# TopSheet.net
KiCad netlist of a schematic drawn in Altium Designer
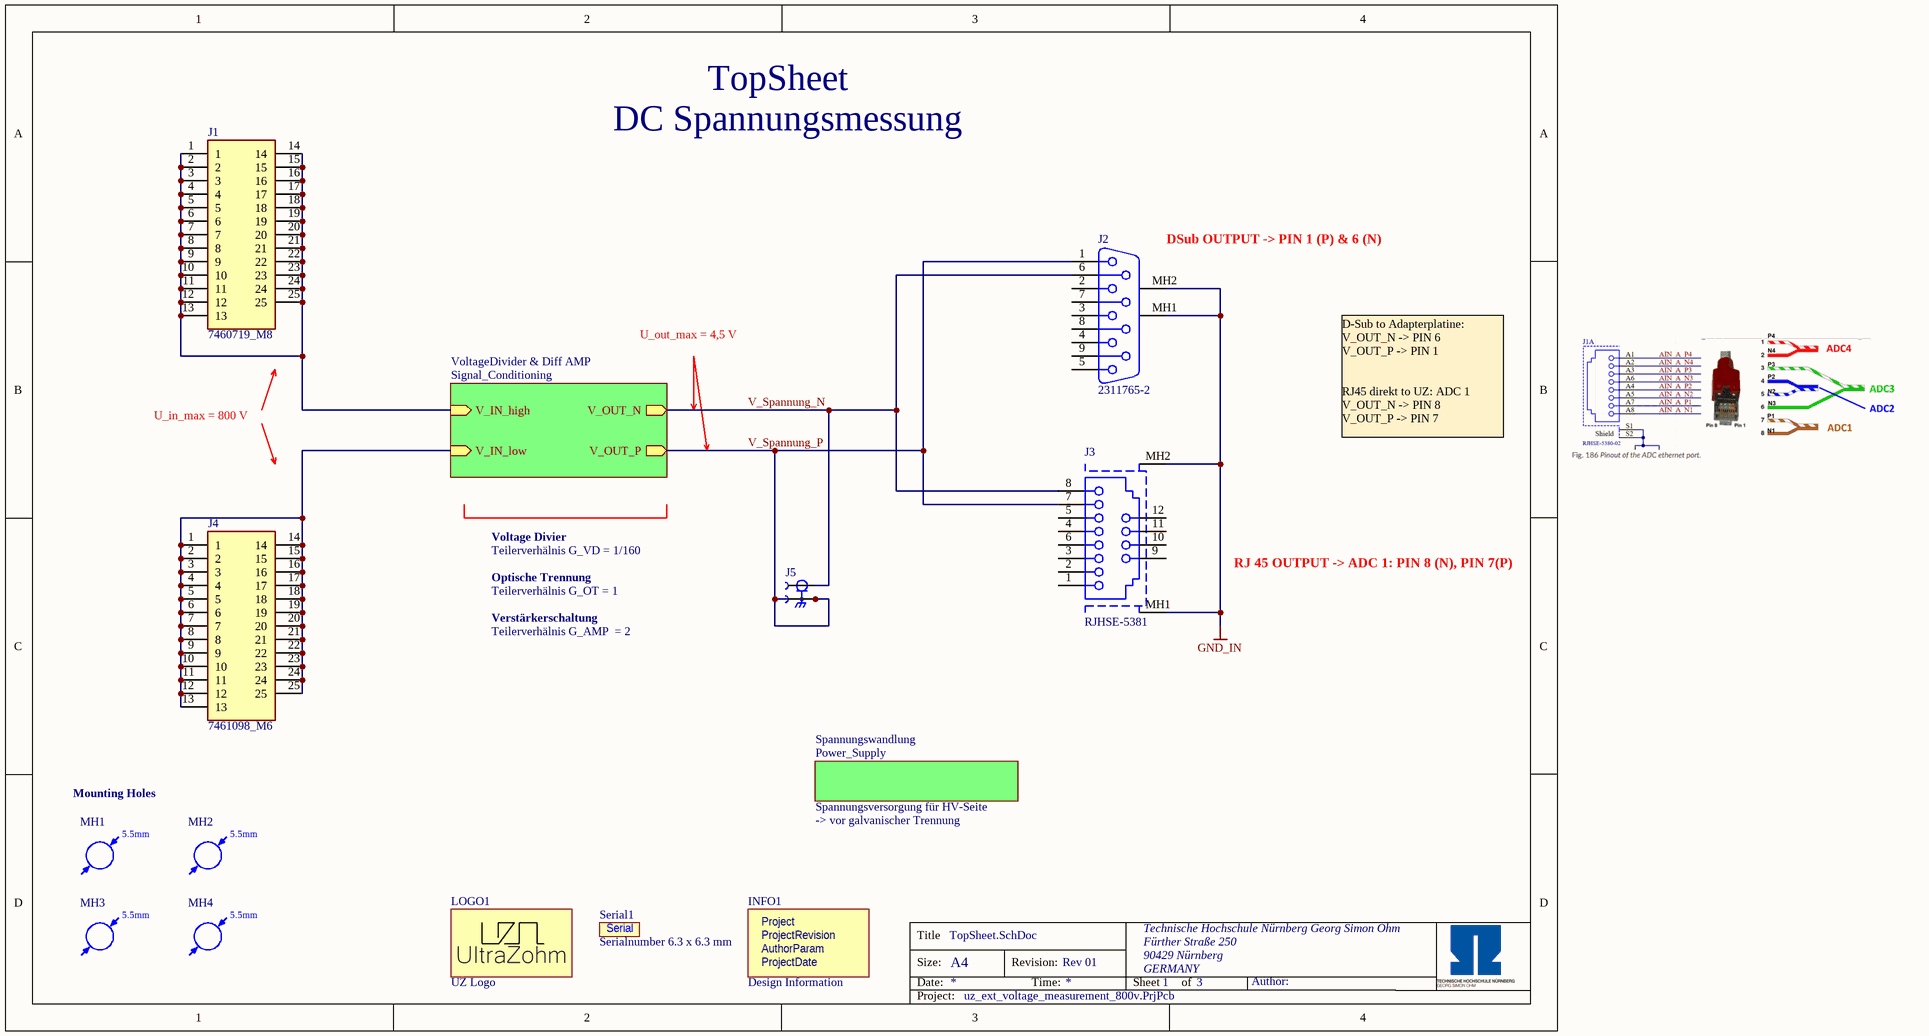
[diagram p0: TopSheet.SchDoc]

(export (version "E")
  (design (tool "Eeschema 10.0.6"))
  (components
    (comp (ref "INFO1")
      (value "Design Information")
      (footprint "Design_info")
      (description "Design InformationS")
      (fields (field (name "MANUFACTURER") "UltraZohm") (field (name "CREATED FROM") "MGremer"))
      (libsource (lib "user") (part "Design_info"))
    )
    (comp (ref "J1")
      (value "7460719_M8")
      (footprint "eigene_lib_alt:7460719")
      (description "Connector")
      (fields
        (field (name "MANUFACTURER_PART_NUMBER") "7460719")
        (field (name "MOUSER PART NUMBER") "710-7460719")
      )
      (libsource (lib "SamacSys") (part "7460719_M8"))
    )
    (comp (ref "J2")
      (value "2311765-2")
      (footprint "eigene_lib_alt:23117652")
      (description "Connector D-Sub 9 Pin Female")
      (fields (field (name "MOUSER PART NUMBER") "571-2311765-2"))
      (libsource (lib "eigene_lib_alt") (part "2311765-2"))
    )
    (comp (ref "J3")
      (value "RJHSE-5381")
      (footprint "eigene_lib_alt:RJHSE-5381")
      (description "Connector Ethernet R/A RJ45 SHIELDED 8 CONT Y/G LEDS")
      (libsource (lib "eigene_lib_alt") (part "RJHSE-5381"))
    )
    (comp (ref "J4")
      (value "7461098_M6")
      (footprint "eigene_lib_alt:7461098")
      (description "Connector")
      (fields
        (field (name "MANUFACTURER_PART_NUMBER") "7461098")
        (field (name "MOUSER PART NUMBER") "710-7461098")
      )
      (libsource (lib "eigene_lib_alt") (part "7461098_M6"))
    )
    (comp (ref "J5")
      (value "BNC5-J-P-GN-ST-TH2D_new")
      (footprint "eigene_lib_alt:BNC5-J-P-GN-ST-TH2D_new")
      (description "BNC Connector")
      (libsource (lib "SamacSys") (part "BNC5-J-P-GN-ST-TH2D_new"))
    )
    (comp (ref "LOGO1")
      (value "UZ Logo")
      (footprint "UZ_Logo_small")
      (fields
        (field (name "MANUFACTURER PART NUMBER") "Logo small")
        (field (name "MANUFACTURER") "UltraZohm")
        (field (name "CREATED") "Jan2021_Liegmann")
        (field (name "CREATED FROM") "MGremer")
      )
      (libsource (lib "user") (part "UZ Logo"))
    )
    (comp (ref "MH1")
      (value "Mounting_Hole_M5")
      (footprint "Mounting_Hole_M5:Mounting Hole (M5)")
      (description "Mounting Hole")
      (libsource (lib "Mounting_Hole_M5") (part "Mounting_Hole_M5"))
    )
    (comp (ref "MH2")
      (value "Mounting_Hole_M5")
      (footprint "Mounting_Hole_M5:Mounting Hole (M5)")
      (description "Mounting Hole")
      (libsource (lib "Mounting_Hole_M5") (part "Mounting_Hole_M5"))
    )
    (comp (ref "MH3")
      (value "Mounting_Hole_M5")
      (footprint "Mounting_Hole_M5:Mounting Hole (M5)")
      (description "Mounting Hole")
      (libsource (lib "Mounting_Hole_M5") (part "Mounting_Hole_M5"))
    )
    (comp (ref "MH4")
      (value "Mounting_Hole_M5")
      (footprint "Mounting_Hole_M5:Mounting Hole (M5)")
      (description "Mounting Hole")
      (libsource (lib "Mounting_Hole_M5") (part "Mounting_Hole_M5"))
    )
    (comp (ref "Serial1")
      (value "Serialnumber 6.3 x 6.3 mm")
      (footprint "SERIAL_6.3X6.3MM")
      (description "Serial Number")
      (fields
        (field (name "MANUFACTURER") "UltraZohm")
        (field (name "CREATED") "2018_09_18_AGeiger")
        (field (name "CREATED FROM") "MGremer")
      )
      (libsource (lib "user") (part "SerialNumber"))
    )
  )
  (nets
    (net (code "1") (name "/V_IN_high") (class "Default")
      (node (ref "J1") (pin "1") (pinfunction "1_1") (pintype "passive"))
      (node (ref "J1") (pin "10") (pinfunction "10_10") (pintype "passive"))
      (node (ref "J1") (pin "11") (pinfunction "11_11") (pintype "passive"))
      (node (ref "J1") (pin "12") (pinfunction "12_12") (pintype "passive"))
      (node (ref "J1") (pin "13") (pinfunction "13_13") (pintype "passive"))
      (node (ref "J1") (pin "14") (pinfunction "14_14") (pintype "passive"))
      (node (ref "J1") (pin "15") (pinfunction "15_15") (pintype "passive"))
      (node (ref "J1") (pin "16") (pinfunction "16_16") (pintype "passive"))
      (node (ref "J1") (pin "17") (pinfunction "17_17") (pintype "passive"))
      (node (ref "J1") (pin "18") (pinfunction "18_18") (pintype "passive"))
      (node (ref "J1") (pin "19") (pinfunction "19_19") (pintype "passive"))
      (node (ref "J1") (pin "2") (pinfunction "2_2") (pintype "passive"))
      (node (ref "J1") (pin "20") (pinfunction "20_20") (pintype "passive"))
      (node (ref "J1") (pin "21") (pinfunction "21_21") (pintype "passive"))
      (node (ref "J1") (pin "22") (pinfunction "22_22") (pintype "passive"))
      (node (ref "J1") (pin "23") (pinfunction "23_23") (pintype "passive"))
      (node (ref "J1") (pin "24") (pinfunction "24_24") (pintype "passive"))
      (node (ref "J1") (pin "25") (pinfunction "25_25") (pintype "passive"))
      (node (ref "J1") (pin "3") (pinfunction "3_3") (pintype "passive"))
      (node (ref "J1") (pin "4") (pinfunction "4_4") (pintype "passive"))
      (node (ref "J1") (pin "5") (pinfunction "5_5") (pintype "passive"))
      (node (ref "J1") (pin "6") (pinfunction "6_6") (pintype "passive"))
      (node (ref "J1") (pin "7") (pinfunction "7_7") (pintype "passive"))
      (node (ref "J1") (pin "8") (pinfunction "8_8") (pintype "passive"))
      (node (ref "J1") (pin "9") (pinfunction "9_9") (pintype "passive"))
    )
    (net (code "2") (name "/V_IN_low") (class "Default")
      (node (ref "J4") (pin "1") (pinfunction "1_1") (pintype "passive"))
      (node (ref "J4") (pin "10") (pinfunction "10_10") (pintype "passive"))
      (node (ref "J4") (pin "11") (pinfunction "11_11") (pintype "passive"))
      (node (ref "J4") (pin "12") (pinfunction "12_12") (pintype "passive"))
      (node (ref "J4") (pin "13") (pinfunction "13_13") (pintype "passive"))
      (node (ref "J4") (pin "14") (pinfunction "14_14") (pintype "passive"))
      (node (ref "J4") (pin "15") (pinfunction "15_15") (pintype "passive"))
      (node (ref "J4") (pin "16") (pinfunction "16_16") (pintype "passive"))
      (node (ref "J4") (pin "17") (pinfunction "17_17") (pintype "passive"))
      (node (ref "J4") (pin "18") (pinfunction "18_18") (pintype "passive"))
      (node (ref "J4") (pin "19") (pinfunction "19_19") (pintype "passive"))
      (node (ref "J4") (pin "2") (pinfunction "2_2") (pintype "passive"))
      (node (ref "J4") (pin "20") (pinfunction "20_20") (pintype "passive"))
      (node (ref "J4") (pin "21") (pinfunction "21_21") (pintype "passive"))
      (node (ref "J4") (pin "22") (pinfunction "22_22") (pintype "passive"))
      (node (ref "J4") (pin "23") (pinfunction "23_23") (pintype "passive"))
      (node (ref "J4") (pin "24") (pinfunction "24_24") (pintype "passive"))
      (node (ref "J4") (pin "25") (pinfunction "25_25") (pintype "passive"))
      (node (ref "J4") (pin "3") (pinfunction "3_3") (pintype "passive"))
      (node (ref "J4") (pin "4") (pinfunction "4_4") (pintype "passive"))
      (node (ref "J4") (pin "5") (pinfunction "5_5") (pintype "passive"))
      (node (ref "J4") (pin "6") (pinfunction "6_6") (pintype "passive"))
      (node (ref "J4") (pin "7") (pinfunction "7_7") (pintype "passive"))
      (node (ref "J4") (pin "8") (pinfunction "8_8") (pintype "passive"))
      (node (ref "J4") (pin "9") (pinfunction "9_9") (pintype "passive"))
    )
    (net (code "3") (name "/V_Spannung_N") (class "Default")
      (node (ref "J2") (pin "6") (pinfunction "6_6") (pintype "passive"))
      (node (ref "J3") (pin "8") (pinfunction "8_8") (pintype "passive"))
      (node (ref "J5") (pin "1") (pinfunction "1_1") (pintype "passive"))
    )
    (net (code "4") (name "/V_Spannung_P") (class "Default")
      (node (ref "J2") (pin "1") (pinfunction "1_1") (pintype "passive"))
      (node (ref "J3") (pin "7") (pinfunction "7_7") (pintype "passive"))
      (node (ref "J5") (pin "S_1") (pinfunction "2_S_1") (pintype "passive"))
      (node (ref "J5") (pin "S_2") (pinfunction "2_S_2") (pintype "passive"))
      (node (ref "J5") (pin "S_3") (pinfunction "2_S_3") (pintype "passive"))
    )
    (net (code "5") (name "GND_IN") (class "Default")
      (node (ref "J2") (pin "MH1") (pinfunction "MH1_MH1") (pintype "passive"))
      (node (ref "J2") (pin "MH2") (pinfunction "MH2_MH2") (pintype "passive"))
      (node (ref "J3") (pin "MH1") (pinfunction "Shell_MH1") (pintype "passive"))
      (node (ref "J3") (pin "MH2") (pinfunction "Shell_MH2") (pintype "passive"))
    )
    (net (code "6") (name "unconnected-(J2-Pad2)") (class "Default")
      (node (ref "J2") (pin "2") (pinfunction "2_2") (pintype "passive"))
    )
    (net (code "7") (name "unconnected-(J2-Pad3)") (class "Default")
      (node (ref "J2") (pin "3") (pinfunction "3_3") (pintype "passive"))
    )
    (net (code "8") (name "unconnected-(J2-Pad4)") (class "Default")
      (node (ref "J2") (pin "4") (pinfunction "4_4") (pintype "passive"))
    )
    (net (code "9") (name "unconnected-(J2-Pad5)") (class "Default")
      (node (ref "J2") (pin "5") (pinfunction "5_5") (pintype "passive"))
    )
    (net (code "10") (name "unconnected-(J2-Pad7)") (class "Default")
      (node (ref "J2") (pin "7") (pinfunction "7_7") (pintype "passive"))
    )
    (net (code "11") (name "unconnected-(J2-Pad8)") (class "Default")
      (node (ref "J2") (pin "8") (pinfunction "8_8") (pintype "passive"))
    )
    (net (code "12") (name "unconnected-(J2-Pad9)") (class "Default")
      (node (ref "J2") (pin "9") (pinfunction "9_9") (pintype "passive"))
    )
    (net (code "13") (name "unconnected-(J3-8-Pad9)") (class "Default")
      (node (ref "J3") (pin "9") (pinfunction "8_9") (pintype "passive"))
    )
    (net (code "14") (name "unconnected-(J3-8-Pad10)") (class "Default")
      (node (ref "J3") (pin "10") (pinfunction "8_10") (pintype "passive"))
    )
    (net (code "15") (name "unconnected-(J3-8-Pad11)") (class "Default")
      (node (ref "J3") (pin "11") (pinfunction "8_11") (pintype "passive"))
    )
    (net (code "16") (name "unconnected-(J3-8-Pad12)") (class "Default")
      (node (ref "J3") (pin "12") (pinfunction "8_12") (pintype "passive"))
    )
    (net (code "17") (name "unconnected-(J3-Pad1)") (class "Default")
      (node (ref "J3") (pin "1") (pinfunction "1_1") (pintype "passive"))
    )
    (net (code "18") (name "unconnected-(J3-Pad2)") (class "Default")
      (node (ref "J3") (pin "2") (pinfunction "2_2") (pintype "passive"))
    )
    (net (code "19") (name "unconnected-(J3-Pad3)") (class "Default")
      (node (ref "J3") (pin "3") (pinfunction "3_3") (pintype "passive"))
    )
    (net (code "20") (name "unconnected-(J3-Pad4)") (class "Default")
      (node (ref "J3") (pin "4") (pinfunction "4_4") (pintype "passive"))
    )
    (net (code "21") (name "unconnected-(J3-Pad5)") (class "Default")
      (node (ref "J3") (pin "5") (pinfunction "5_5") (pintype "passive"))
    )
    (net (code "22") (name "unconnected-(J3-Pad6)") (class "Default")
      (node (ref "J3") (pin "6") (pinfunction "6_6") (pintype "passive"))
    )
  )
)
